# SIM800.net
KiCad netlist of a schematic drawn in Altium Designer
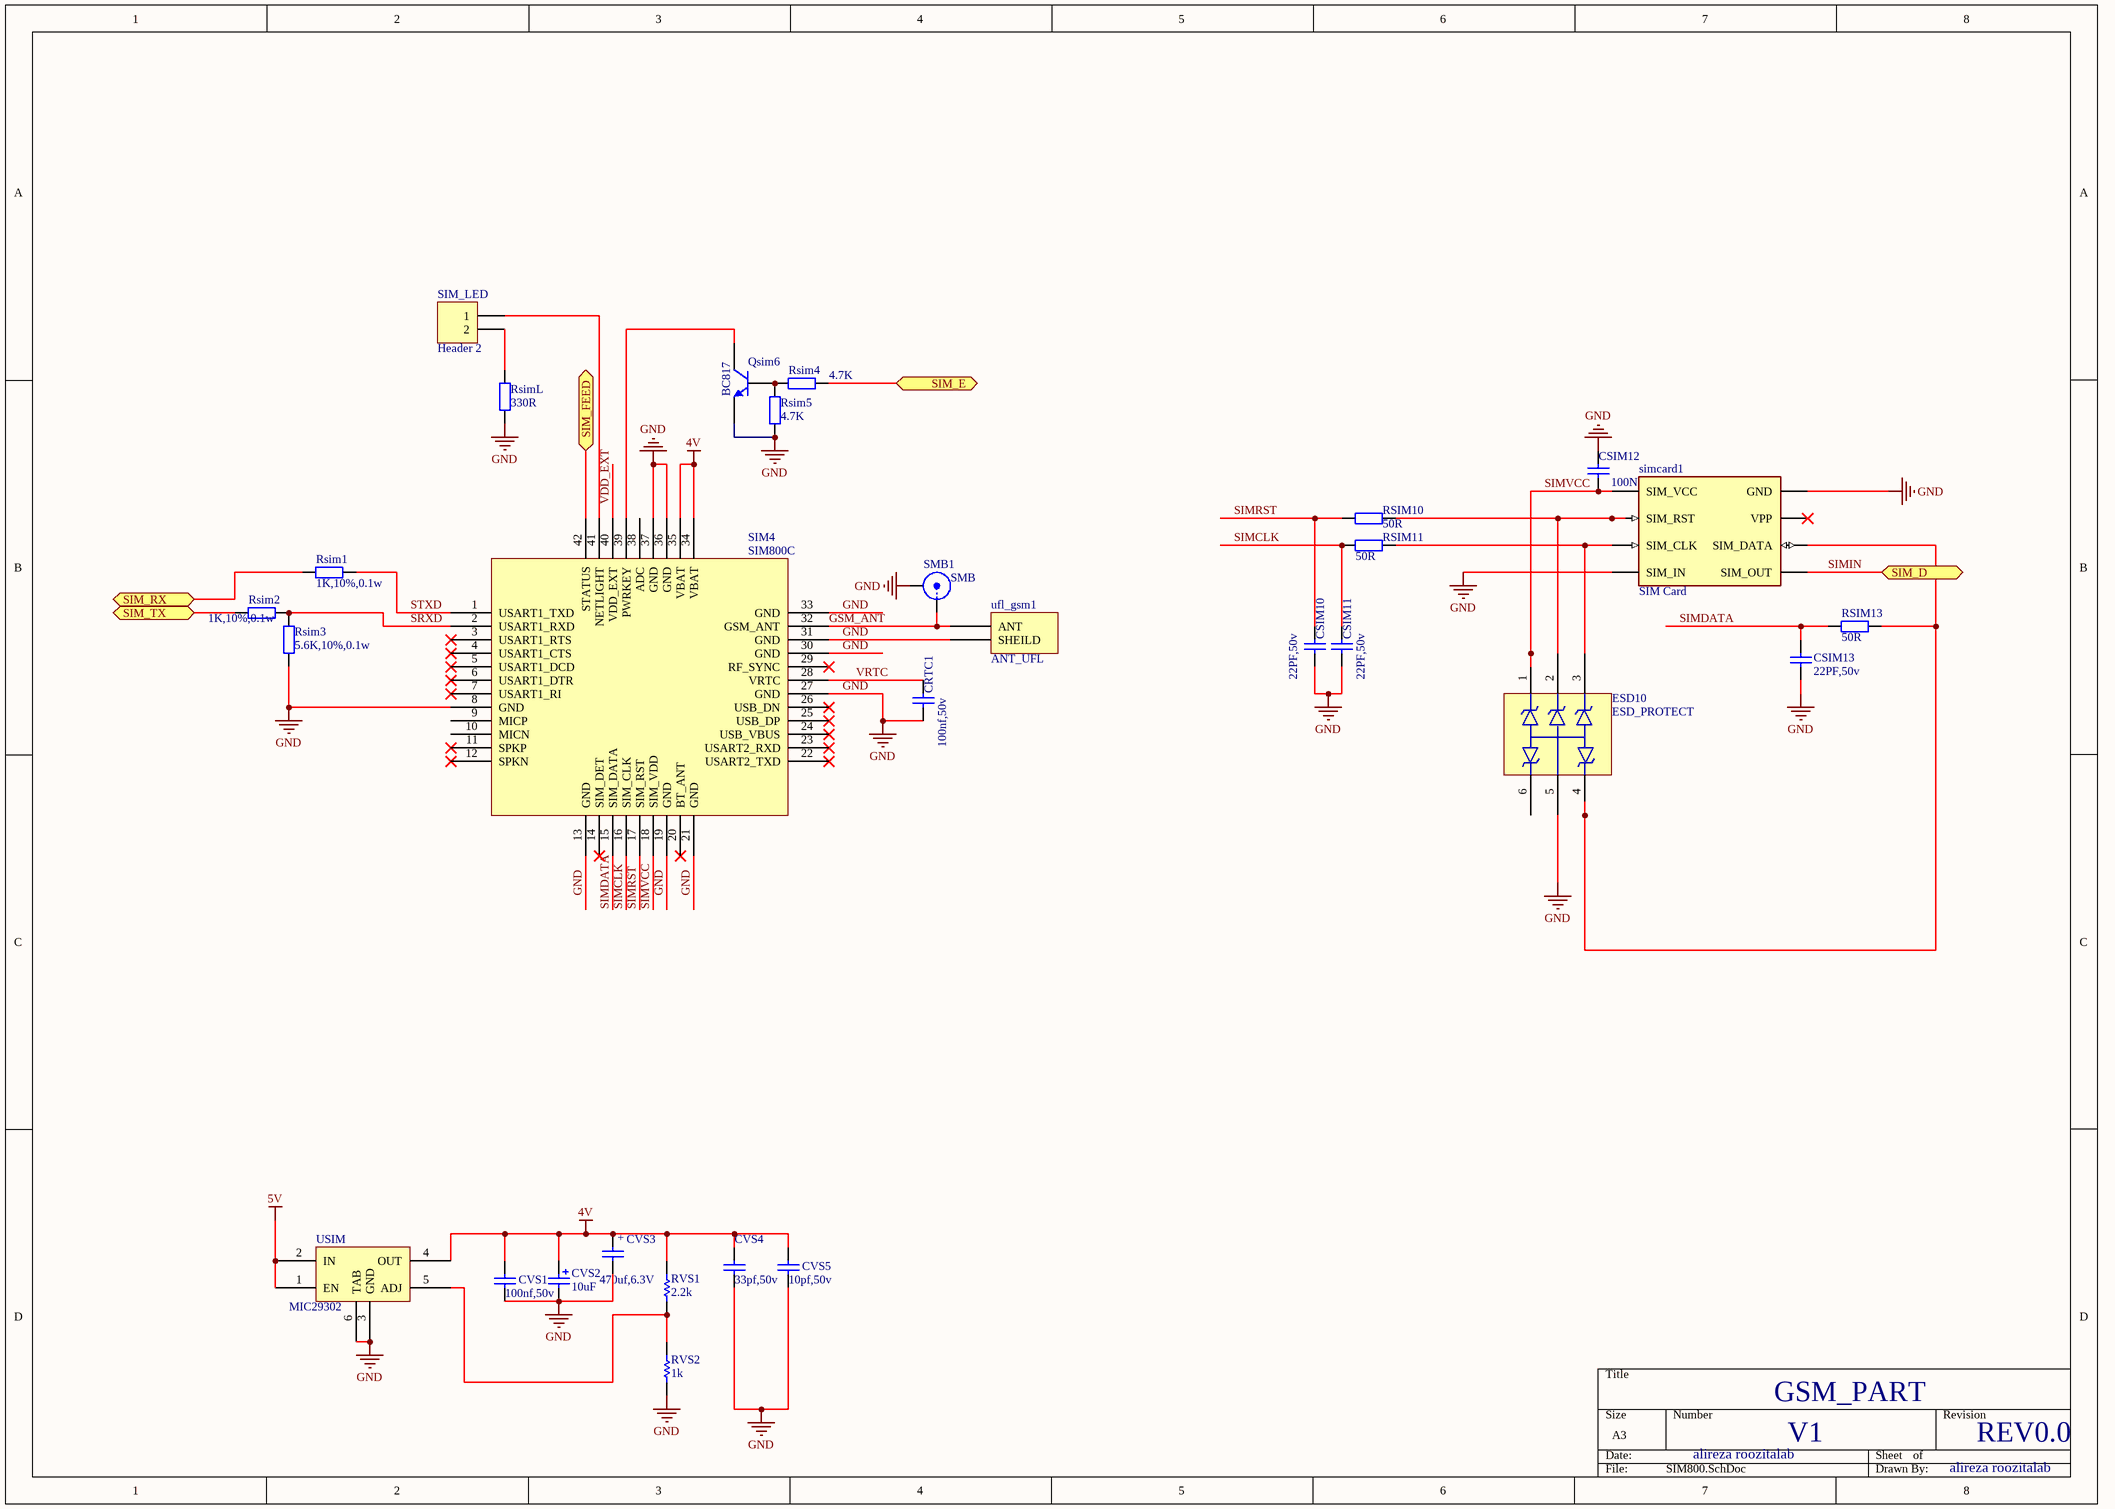
[diagram p0: SIM800.SchDoc]

(export (version "E")
  (design (tool "Eeschema 10.0.6"))
  (components
    (comp (ref "CRTC1")
      (value "100nf,50v")
      (footprint "0805.")
      (description "Capacitor")
      (fields (field (name "PUBLISHER") "Altium Limited"))
      (libsource (lib "MBIO-SCHPCB-MBFD-REV1") (part "Cap"))
    )
    (comp (ref "CSIM10")
      (value "22PF,50v")
      (footprint "0805.")
      (description "Capacitor")
      (fields (field (name "PUBLISHER") "Altium Limited"))
      (libsource (lib "MBIO-SCHPCB-MBFD-REV1") (part "Cap"))
    )
    (comp (ref "CSIM11")
      (value "22PF,50v")
      (footprint "0805.")
      (description "Capacitor")
      (fields (field (name "PUBLISHER") "Altium Limited"))
      (libsource (lib "MBIO-SCHPCB-MBFD-REV1") (part "Cap"))
    )
    (comp (ref "CSIM12")
      (value "100N")
      (footprint "0805.")
      (description "Capacitor")
      (fields (field (name "PUBLISHER") "Altium Limited"))
      (libsource (lib "MBIO-SCHPCB-MBFD-REV1") (part "Cap"))
    )
    (comp (ref "CSIM13")
      (value "22PF,50v")
      (footprint "0805.")
      (description "Capacitor")
      (fields (field (name "PUBLISHER") "Altium Limited"))
      (libsource (lib "MBIO-SCHPCB-MBFD-REV1") (part "Cap"))
    )
    (comp (ref "CVS1")
      (value "100nf,50v")
      (footprint "0805.")
      (description "Capacitor")
      (fields (field (name "PUBLISHER") "Altium Limited"))
      (libsource (lib "MBIO-SCHPCB-MBFD-REV1") (part "Cap"))
    )
    (comp (ref "CVS2")
      (value "10uF")
      (footprint "C1206.")
      (description "Polarized Capacitor (Radial)")
      (fields (field (name "PUBLISHER") "Altium Limited"))
      (libsource (lib "PCB_Project1") (part "Cap Pol1"))
    )
    (comp (ref "CVS3")
      (value "470uf,6.3V")
      (footprint "MY_SMC_D")
      (description "Polar capacitor")
      (fields (field (name "ASID PART NUMBER") "C-AS"))
      (libsource (lib "TPS54331") (part "Cap Pol"))
    )
    (comp (ref "CVS4")
      (value "33pf,50v")
      (footprint "0805.")
      (description "Capacitor")
      (fields (field (name "PUBLISHER") "Altium Limited"))
      (libsource (lib "MBIO-SCHPCB-MBFD-REV1") (part "Cap"))
    )
    (comp (ref "CVS5")
      (value "10pf,50v")
      (footprint "0805.")
      (description "Capacitor")
      (fields (field (name "PUBLISHER") "Altium Limited"))
      (libsource (lib "MBIO-SCHPCB-MBFD-REV1") (part "Cap"))
    )
    (comp (ref "ESD10")
      (value "ESD_PROTECT")
      (footprint "SMF05")
      (libsource (lib "armlib") (part "ESD_PROTECT"))
    )
    (comp (ref "Qsim6")
      (value "BC817")
      (footprint "2N3906_SMD")
      (description "NPN General Purpose Amplifier")
      (fields (field (name "PUBLISHER") "Altium Limited"))
      (libsource (lib "Miscellaneous Devices") (part "2N3904"))
    )
    (comp (ref "Rsim1")
      (value "1K,10%,0.1w")
      (footprint "0805.")
      (description "Resistor")
      (fields (field (name "PUBLISHER") "Altium Limited"))
      (libsource (lib "") (part "Res2_3"))
    )
    (comp (ref "Rsim2")
      (value "1K,10%,0.1w")
      (footprint "0805.")
      (description "Resistor")
      (fields (field (name "PUBLISHER") "Altium Limited"))
      (libsource (lib "MBIO-SCHPCB-MBFD-REV1") (part "Res2"))
    )
    (comp (ref "Rsim3")
      (value "5.6K,10%,0.1w")
      (footprint "0805.")
      (description "Resistor")
      (fields (field (name "PUBLISHER") "Altium Limited"))
      (libsource (lib "") (part "Res2_1"))
    )
    (comp (ref "Rsim4")
      (value "4.7K")
      (footprint "0805.")
      (description "Resistor")
      (fields (field (name "Comment") "10K,10%,0.1w") (field (name "PUBLISHER") "Altium Limited"))
      (libsource (lib "") (part "Res2_2"))
    )
    (comp (ref "Rsim5")
      (value "4.7K")
      (footprint "0805.")
      (description "Resistor")
      (fields (field (name "Comment") "10K,10%,0.1w") (field (name "PUBLISHER") "Altium Limited"))
      (libsource (lib "MBIO-SCHPCB-MBFD-REV1") (part "Res2"))
    )
    (comp (ref "RSIM10")
      (value "50R")
      (footprint "0805.")
      (description "Resistor")
      (fields (field (name "Comment") "47R,10%,0.1w") (field (name "PUBLISHER") "Altium Limited"))
      (libsource (lib "PCB_Project1") (part "Res2"))
    )
    (comp (ref "RSIM11")
      (value "50R")
      (footprint "0805.")
      (description "Resistor")
      (fields (field (name "Comment") "47R,10%,0.1w") (field (name "PUBLISHER") "Altium Limited"))
      (libsource (lib "PCB_Project1") (part "Res2"))
    )
    (comp (ref "RSIM13")
      (value "50R")
      (footprint "0805.")
      (description "Resistor")
      (fields (field (name "Comment") "47R,10%,0.1w") (field (name "PUBLISHER") "Altium Limited"))
      (libsource (lib "PCB_Project1") (part "Res2"))
    )
    (comp (ref "RsimL")
      (value "330R")
      (footprint "0805.")
      (description "Resistor")
      (fields (field (name "Comment") "330R,10%,0.1w") (field (name "PUBLISHER") "Altium Limited"))
      (libsource (lib "MBIO-SCHPCB-MBFD-REV1") (part "Res2"))
    )
    (comp (ref "RVS1")
      (value "2.2k")
      (footprint "0805.")
      (description "Resistor")
      (fields (field (name "PUBLISHER") "Altium Limited"))
      (libsource (lib "PCB_Project1") (part "Res1"))
    )
    (comp (ref "RVS2")
      (value "1k")
      (footprint "0805.")
      (description "Resistor")
      (fields (field (name "PUBLISHER") "Altium Limited"))
      (libsource (lib "PCB_Project1") (part "Res1"))
    )
    (comp (ref "SIM4") (value "SIM800C") (footprint "SIM800C") (libsource (lib "armlib") (part "SIM800C")))
    (comp (ref "simcard1")
      (value "SIM Card")
      (footprint "MY_SIMCARD")
      (description "Sim Card")
      (libsource (lib "Mylib") (part "SIM Card"))
    )
    (comp (ref "SIM_LED")
      (value "Header 2")
      (footprint "HDR1X2")
      (description "Header, 2-Pin")
      (fields (field (name "PUBLISHER") "Altium Limited"))
      (libsource (lib "Miscellaneous Connectors") (part "Header 2"))
    )
    (comp (ref "SMB1")
      (value "SMB")
      (footprint "SMB_V-RJ45")
      (description "SMB Straight Connector")
      (fields (field (name "PUBLISHER") "Altium Limited"))
      (libsource (lib "Miscellaneous Connectors") (part "SMB"))
    )
    (comp (ref "ufl_gsm1")
      (value "ANT_UFL")
      (footprint "UFL_CON")
      (libsource (lib "armlib") (part "ANT_UFL"))
    )
    (comp (ref "USIM") (value "MIC29302") (footprint "MIC29302") (libsource (lib "armlib") (part "MIC29302")))
  )
  (nets
    (net (code "1") (name "/GSM_ANT") (class "Default")
      (node (ref "SIM4") (pin "32") (pinfunction "GSM_ANT_32") (pintype "passive"))
      (node (ref "SMB1") (pin "1") (pinfunction "X_1") (pintype "passive"))
      (node (ref "ufl_gsm1") (pin "2") (pinfunction "ANT_2") (pintype "passive"))
    )
    (net (code "2") (name "/SIMCLK") (class "Default")
      (node (ref "CSIM11") (pin "2") (pinfunction "2_2") (pintype "passive"))
      (node (ref "RSIM11") (pin "1") (pinfunction "1_1") (pintype "passive"))
      (node (ref "SIM4") (pin "16") (pinfunction "SIM_CLK_16") (pintype "passive"))
    )
    (net (code "3") (name "/SIMDATA") (class "Default")
      (node (ref "CSIM13") (pin "2") (pinfunction "2_2") (pintype "passive"))
      (node (ref "RSIM13") (pin "1") (pinfunction "1_1") (pintype "passive"))
      (node (ref "SIM4") (pin "15") (pinfunction "SIM_DATA_15") (pintype "passive"))
    )
    (net (code "4") (name "/SIMIN") (class "Default")
      (node (ref "simcard1") (pin "C8") (pinfunction "SIM_OUT_C8") (pintype "passive"))
    )
    (net (code "5") (name "/SIMRST") (class "Default")
      (node (ref "CSIM10") (pin "2") (pinfunction "2_2") (pintype "passive"))
      (node (ref "RSIM10") (pin "1") (pinfunction "1_1") (pintype "passive"))
      (node (ref "SIM4") (pin "17") (pinfunction "SIM_RST_17") (pintype "passive"))
    )
    (net (code "6") (name "/SIMVCC") (class "Default")
      (node (ref "CSIM12") (pin "1") (pinfunction "1_1") (pintype "passive"))
      (node (ref "ESD10") (pin "1") (pinfunction "1_1") (pintype "passive"))
      (node (ref "SIM4") (pin "18") (pinfunction "SIM_VDD_18") (pintype "passive"))
      (node (ref "simcard1") (pin "C1") (pinfunction "SIM_VCC_C1") (pintype "power_in"))
    )
    (net (code "7") (name "/SIM_E") (class "Default")
      (node (ref "Rsim4") (pin "1") (pinfunction "1_1") (pintype "passive"))
    )
    (net (code "8") (name "/SIM_FEED") (class "Default")
      (node (ref "SIM4") (pin "42") (pinfunction "STATUS_42") (pintype "passive"))
    )
    (net (code "9") (name "/SIM_RX") (class "Default")
      (node (ref "Rsim1") (pin "2") (pinfunction "2_2") (pintype "passive"))
    )
    (net (code "10") (name "/SIM_TX") (class "Default")
      (node (ref "Rsim2") (pin "1") (pinfunction "1_1") (pintype "passive"))
    )
    (net (code "11") (name "/SRXD") (class "Default")
      (node (ref "Rsim2") (pin "2") (pinfunction "2_2") (pintype "passive"))
      (node (ref "Rsim3") (pin "2") (pinfunction "2_2") (pintype "passive"))
      (node (ref "SIM4") (pin "2") (pinfunction "USART1_RXD_2") (pintype "passive"))
    )
    (net (code "12") (name "/STXD") (class "Default")
      (node (ref "Rsim1") (pin "1") (pinfunction "1_1") (pintype "passive"))
      (node (ref "SIM4") (pin "1") (pinfunction "USART1_TXD_1") (pintype "passive"))
    )
    (net (code "13") (name "/VDD_EXT") (class "Default")
      (node (ref "SIM4") (pin "40") (pinfunction "VDD_EXT_40") (pintype "passive"))
    )
    (net (code "14") (name "/VRTC") (class "Default")
      (node (ref "CRTC1") (pin "2") (pinfunction "2_2") (pintype "passive"))
      (node (ref "SIM4") (pin "28") (pinfunction "VRTC_28") (pintype "passive"))
    )
    (net (code "15") (name "4V") (class "Default")
      (node (ref "CVS1") (pin "2") (pinfunction "2_2") (pintype "passive"))
      (node (ref "CVS2") (pin "1") (pinfunction "1_1") (pintype "passive"))
      (node (ref "CVS3") (pin "+") (pinfunction "+_+") (pintype "passive"))
      (node (ref "CVS4") (pin "2") (pinfunction "2_2") (pintype "passive"))
      (node (ref "CVS5") (pin "2") (pinfunction "2_2") (pintype "passive"))
      (node (ref "RVS1") (pin "2") (pinfunction "2_2") (pintype "passive"))
      (node (ref "SIM4") (pin "34") (pinfunction "VBAT_34") (pintype "passive"))
      (node (ref "SIM4") (pin "35") (pinfunction "VBAT_35") (pintype "passive"))
      (node (ref "USIM") (pin "4") (pinfunction "OUT_4") (pintype "passive"))
    )
    (net (code "16") (name "5V") (class "Default")
      (node (ref "USIM") (pin "1") (pinfunction "EN_1") (pintype "passive"))
      (node (ref "USIM") (pin "2") (pinfunction "IN_2") (pintype "passive"))
    )
    (net (code "17") (name "GND") (class "Default")
      (node (ref "CRTC1") (pin "1") (pinfunction "1_1") (pintype "passive"))
      (node (ref "CSIM10") (pin "1") (pinfunction "1_1") (pintype "passive"))
      (node (ref "CSIM11") (pin "1") (pinfunction "1_1") (pintype "passive"))
      (node (ref "CSIM12") (pin "2") (pinfunction "2_2") (pintype "passive"))
      (node (ref "CSIM13") (pin "1") (pinfunction "1_1") (pintype "passive"))
      (node (ref "CVS1") (pin "1") (pinfunction "1_1") (pintype "passive"))
      (node (ref "CVS2") (pin "2") (pinfunction "2_2") (pintype "passive"))
      (node (ref "CVS3") (pin "-") (pinfunction "-_-") (pintype "passive"))
      (node (ref "CVS4") (pin "1") (pinfunction "1_1") (pintype "passive"))
      (node (ref "CVS5") (pin "1") (pinfunction "1_1") (pintype "passive"))
      (node (ref "ESD10") (pin "5") (pinfunction "5_5") (pintype "passive"))
      (node (ref "Qsim6") (pin "1") (pinfunction "E_1") (pintype "passive"))
      (node (ref "RVS2") (pin "1") (pinfunction "1_1") (pintype "passive"))
      (node (ref "Rsim3") (pin "1") (pinfunction "1_1") (pintype "passive"))
      (node (ref "Rsim5") (pin "1") (pinfunction "1_1") (pintype "passive"))
      (node (ref "RsimL") (pin "1") (pinfunction "1_1") (pintype "passive"))
      (node (ref "SIM4") (pin "13") (pinfunction "GND_13") (pintype "passive"))
      (node (ref "SIM4") (pin "19") (pinfunction "GND_19") (pintype "passive"))
      (node (ref "SIM4") (pin "21") (pinfunction "GND_21") (pintype "passive"))
      (node (ref "SIM4") (pin "27") (pinfunction "GND_27") (pintype "passive"))
      (node (ref "SIM4") (pin "30") (pinfunction "GND_30") (pintype "passive"))
      (node (ref "SIM4") (pin "31") (pinfunction "GND_31") (pintype "passive"))
      (node (ref "SIM4") (pin "33") (pinfunction "GND_33") (pintype "passive"))
      (node (ref "SIM4") (pin "36") (pinfunction "GND_36") (pintype "passive"))
      (node (ref "SIM4") (pin "37") (pinfunction "GND_37") (pintype "passive"))
      (node (ref "SIM4") (pin "8") (pinfunction "GND_8") (pintype "passive"))
      (node (ref "SMB1") (pin "2") (pinfunction "Y_2") (pintype "passive"))
      (node (ref "USIM") (pin "3") (pinfunction "GND_3") (pintype "passive"))
      (node (ref "USIM") (pin "6") (pinfunction "TAB_6") (pintype "passive"))
      (node (ref "simcard1") (pin "C4") (pinfunction "SIM_IN_C4") (pintype "passive"))
      (node (ref "simcard1") (pin "C5") (pinfunction "GND_C5") (pintype "power_in"))
      (node (ref "ufl_gsm1") (pin "1") (pinfunction "SHEILD_1") (pintype "passive"))
    )
    (net (code "18") (name "Net-(Qsim6-B)") (class "Default")
      (node (ref "Qsim6") (pin "2") (pinfunction "B_2") (pintype "passive"))
      (node (ref "Rsim4") (pin "2") (pinfunction "2_2") (pintype "passive"))
      (node (ref "Rsim5") (pin "2") (pinfunction "2_2") (pintype "passive"))
    )
    (net (code "19") (name "Net-(Qsim6-C)") (class "Default")
      (node (ref "Qsim6") (pin "3") (pinfunction "C_3") (pintype "passive"))
      (node (ref "SIM4") (pin "39") (pinfunction "PWRKEY_39") (pintype "passive"))
    )
    (net (code "20") (name "Net-(RsimL-Pad2)") (class "Default")
      (node (ref "RsimL") (pin "2") (pinfunction "2_2") (pintype "passive"))
      (node (ref "SIM_LED") (pin "2") (pinfunction "2_2") (pintype "passive"))
    )
    (net (code "21") (name "Net-(SIM4-NETLIGHT)") (class "Default")
      (node (ref "SIM4") (pin "41") (pinfunction "NETLIGHT_41") (pintype "passive"))
      (node (ref "SIM_LED") (pin "1") (pinfunction "1_1") (pintype "passive"))
    )
    (net (code "22") (name "Net-(USIM-ADJ)") (class "Default")
      (node (ref "RVS1") (pin "1") (pinfunction "1_1") (pintype "passive"))
      (node (ref "RVS2") (pin "2") (pinfunction "2_2") (pintype "passive"))
      (node (ref "USIM") (pin "5") (pinfunction "ADJ_5") (pintype "passive"))
    )
    (net (code "23") (name "Net-(simcard1-SIM_CLK)") (class "Default")
      (node (ref "ESD10") (pin "3") (pinfunction "3_3") (pintype "passive"))
      (node (ref "RSIM11") (pin "2") (pinfunction "2_2") (pintype "passive"))
      (node (ref "simcard1") (pin "C3") (pinfunction "SIM_CLK_C3") (pintype "input"))
    )
    (net (code "24") (name "Net-(simcard1-SIM_DATA)") (class "Default")
      (node (ref "ESD10") (pin "4") (pinfunction "4_4") (pintype "passive"))
      (node (ref "RSIM13") (pin "2") (pinfunction "2_2") (pintype "passive"))
      (node (ref "simcard1") (pin "C7") (pinfunction "SIM_DATA_C7") (pintype "bidirectional"))
    )
    (net (code "25") (name "Net-(simcard1-SIM_RST)") (class "Default")
      (node (ref "ESD10") (pin "2") (pinfunction "2_2") (pintype "passive"))
      (node (ref "RSIM10") (pin "2") (pinfunction "2_2") (pintype "passive"))
      (node (ref "simcard1") (pin "C2") (pinfunction "SIM_RST_C2") (pintype "input"))
    )
    (net (code "26") (name "unconnected-(ESD10-Pad6)") (class "Default")
      (node (ref "ESD10") (pin "6") (pinfunction "6_6") (pintype "passive"))
    )
    (net (code "27") (name "unconnected-(SIM4-ADC-Pad38)") (class "Default")
      (node (ref "SIM4") (pin "38") (pinfunction "ADC_38") (pintype "passive"))
    )
    (net (code "28") (name "unconnected-(SIM4-BT_ANT-Pad20)") (class "Default")
      (node (ref "SIM4") (pin "20") (pinfunction "BT_ANT_20") (pintype "passive+no_connect"))
    )
    (net (code "29") (name "unconnected-(SIM4-MICN-Pad10)") (class "Default")
      (node (ref "SIM4") (pin "10") (pinfunction "MICN_10") (pintype "passive"))
    )
    (net (code "30") (name "unconnected-(SIM4-MICP-Pad9)") (class "Default")
      (node (ref "SIM4") (pin "9") (pinfunction "MICP_9") (pintype "passive"))
    )
    (net (code "31") (name "unconnected-(SIM4-RF_SYNC-Pad29)") (class "Default")
      (node (ref "SIM4") (pin "29") (pinfunction "RF_SYNC_29") (pintype "passive+no_connect"))
    )
    (net (code "32") (name "unconnected-(SIM4-SIM_DET-Pad14)") (class "Default")
      (node (ref "SIM4") (pin "14") (pinfunction "SIM_DET_14") (pintype "passive+no_connect"))
    )
    (net (code "33") (name "unconnected-(SIM4-SPKN-Pad12)") (class "Default")
      (node (ref "SIM4") (pin "12") (pinfunction "SPKN_12") (pintype "passive+no_connect"))
    )
    (net (code "34") (name "unconnected-(SIM4-SPKP-Pad11)") (class "Default")
      (node (ref "SIM4") (pin "11") (pinfunction "SPKP_11") (pintype "passive+no_connect"))
    )
    (net (code "35") (name "unconnected-(SIM4-USART1_CTS-Pad4)") (class "Default")
      (node (ref "SIM4") (pin "4") (pinfunction "USART1_CTS_4") (pintype "passive+no_connect"))
    )
    (net (code "36") (name "unconnected-(SIM4-USART1_DCD-Pad5)") (class "Default")
      (node (ref "SIM4") (pin "5") (pinfunction "USART1_DCD_5") (pintype "passive+no_connect"))
    )
    (net (code "37") (name "unconnected-(SIM4-USART1_DTR-Pad6)") (class "Default")
      (node (ref "SIM4") (pin "6") (pinfunction "USART1_DTR_6") (pintype "passive+no_connect"))
    )
    (net (code "38") (name "unconnected-(SIM4-USART1_RI-Pad7)") (class "Default")
      (node (ref "SIM4") (pin "7") (pinfunction "USART1_RI_7") (pintype "passive+no_connect"))
    )
    (net (code "39") (name "unconnected-(SIM4-USART1_RTS-Pad3)") (class "Default")
      (node (ref "SIM4") (pin "3") (pinfunction "USART1_RTS_3") (pintype "passive+no_connect"))
    )
    (net (code "40") (name "unconnected-(SIM4-USART2_RXD-Pad23)") (class "Default")
      (node (ref "SIM4") (pin "23") (pinfunction "USART2_RXD_23") (pintype "passive+no_connect"))
    )
    (net (code "41") (name "unconnected-(SIM4-USART2_TXD-Pad22)") (class "Default")
      (node (ref "SIM4") (pin "22") (pinfunction "USART2_TXD_22") (pintype "passive+no_connect"))
    )
    (net (code "42") (name "unconnected-(SIM4-USB_DN-Pad26)") (class "Default")
      (node (ref "SIM4") (pin "26") (pinfunction "USB_DN_26") (pintype "passive+no_connect"))
    )
    (net (code "43") (name "unconnected-(SIM4-USB_DP-Pad25)") (class "Default")
      (node (ref "SIM4") (pin "25") (pinfunction "USB_DP_25") (pintype "passive+no_connect"))
    )
    (net (code "44") (name "unconnected-(SIM4-USB_VBUS-Pad24)") (class "Default")
      (node (ref "SIM4") (pin "24") (pinfunction "USB_VBUS_24") (pintype "passive+no_connect"))
    )
    (net (code "45") (name "unconnected-(simcard1-VPP-PadC6)") (class "Default")
      (node (ref "simcard1") (pin "C6") (pinfunction "VPP_C6") (pintype "passive+no_connect"))
    )
  )
)
